# prox_board.net
KiCad netlist of a schematic drawn in EAGLE
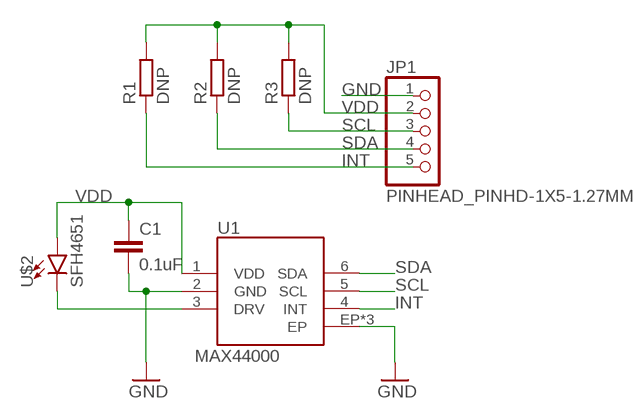
[diagram p0: schematic, sheet 1]

(export (version "E")
  (design (tool "Eeschema 10.0.6"))
  (components
    (comp (ref "C1")
      (value "0.1uF")
      (footprint "eagle-import:C0603")
      (libsource (lib "eagle-import") (part "C-EUC0603"))
    )
    (comp (ref "JP1")
      (value "PINHEAD_PINHD-1X5-1.27MM")
      (footprint "eagle-import:PINHEAD_1X05-1.27MM")
      (libsource (lib "eagle-import") (part "PINHEAD_PINHD-1X5-1.27MM"))
    )
    (comp (ref "R1")
      (value "DNP")
      (footprint "eagle-import:R0603")
      (libsource (lib "eagle-import") (part "R-EU_R0603"))
    )
    (comp (ref "R2")
      (value "DNP")
      (footprint "eagle-import:R0603")
      (libsource (lib "eagle-import") (part "R-EU_R0603"))
    )
    (comp (ref "R3")
      (value "DNP")
      (footprint "eagle-import:R0603")
      (libsource (lib "eagle-import") (part "R-EU_R0603"))
    )
    (comp (ref "U$2")
      (value "SFH4651")
      (footprint "eagle-import:MIDLED")
      (libsource (lib "eagle-import") (part "SFH4651"))
    )
    (comp (ref "U1")
      (value "MAX44000")
      (footprint "eagle-import:6OTDFN-EP")
      (libsource (lib "eagle-import") (part "MAX44000"))
    )
  )
  (nets
    (net (code "1") (name "/INT") (class "Default")
      (node (ref "JP1") (pin "5") (pinfunction "5_5") (pintype "passive"))
      (node (ref "R1") (pin "1") (pinfunction "1_1") (pintype "passive"))
      (node (ref "U1") (pin "4") (pinfunction "INT_4") (pintype "bidirectional"))
    )
    (net (code "2") (name "/SCL") (class "Default")
      (node (ref "JP1") (pin "3") (pinfunction "3_3") (pintype "passive"))
      (node (ref "R3") (pin "1") (pinfunction "1_1") (pintype "passive"))
      (node (ref "U1") (pin "5") (pinfunction "SCL_5") (pintype "bidirectional"))
    )
    (net (code "3") (name "/SDA") (class "Default")
      (node (ref "JP1") (pin "4") (pinfunction "4_4") (pintype "passive"))
      (node (ref "R2") (pin "1") (pinfunction "1_1") (pintype "passive"))
      (node (ref "U1") (pin "6") (pinfunction "SDA_6") (pintype "bidirectional"))
    )
    (net (code "4") (name "/VDD") (class "Default")
      (node (ref "C1") (pin "1") (pinfunction "1_1") (pintype "passive"))
      (node (ref "JP1") (pin "2") (pinfunction "2_2") (pintype "passive"))
      (node (ref "R1") (pin "2") (pinfunction "2_2") (pintype "passive"))
      (node (ref "R2") (pin "2") (pinfunction "2_2") (pintype "passive"))
      (node (ref "R3") (pin "2") (pinfunction "2_2") (pintype "passive"))
      (node (ref "U$2") (pin "A") (pinfunction "A_A") (pintype "passive"))
      (node (ref "U1") (pin "1") (pinfunction "VDD_1") (pintype "bidirectional"))
    )
    (net (code "5") (name "GND") (class "Default")
      (node (ref "C1") (pin "2") (pinfunction "2_2") (pintype "passive"))
      (node (ref "JP1") (pin "1") (pinfunction "1_1") (pintype "passive"))
      (node (ref "U1") (pin "2") (pinfunction "GND_2") (pintype "bidirectional"))
      (node (ref "U1") (pin "EP") (pinfunction "EP_EP") (pintype "bidirectional"))
      (node (ref "U1") (pin "P$1") (pinfunction "EP_P$1") (pintype "bidirectional"))
      (node (ref "U1") (pin "P$2") (pinfunction "EP_P$2") (pintype "bidirectional"))
    )
    (net (code "6") (name "Net-(U1-DRV)") (class "Default")
      (node (ref "U$2") (pin "C") (pinfunction "C_C") (pintype "passive"))
      (node (ref "U1") (pin "3") (pinfunction "DRV_3") (pintype "bidirectional"))
    )
  )
)
